# Survey_bicycle_Power.net
KiCad netlist of a schematic drawn in Altium Designer
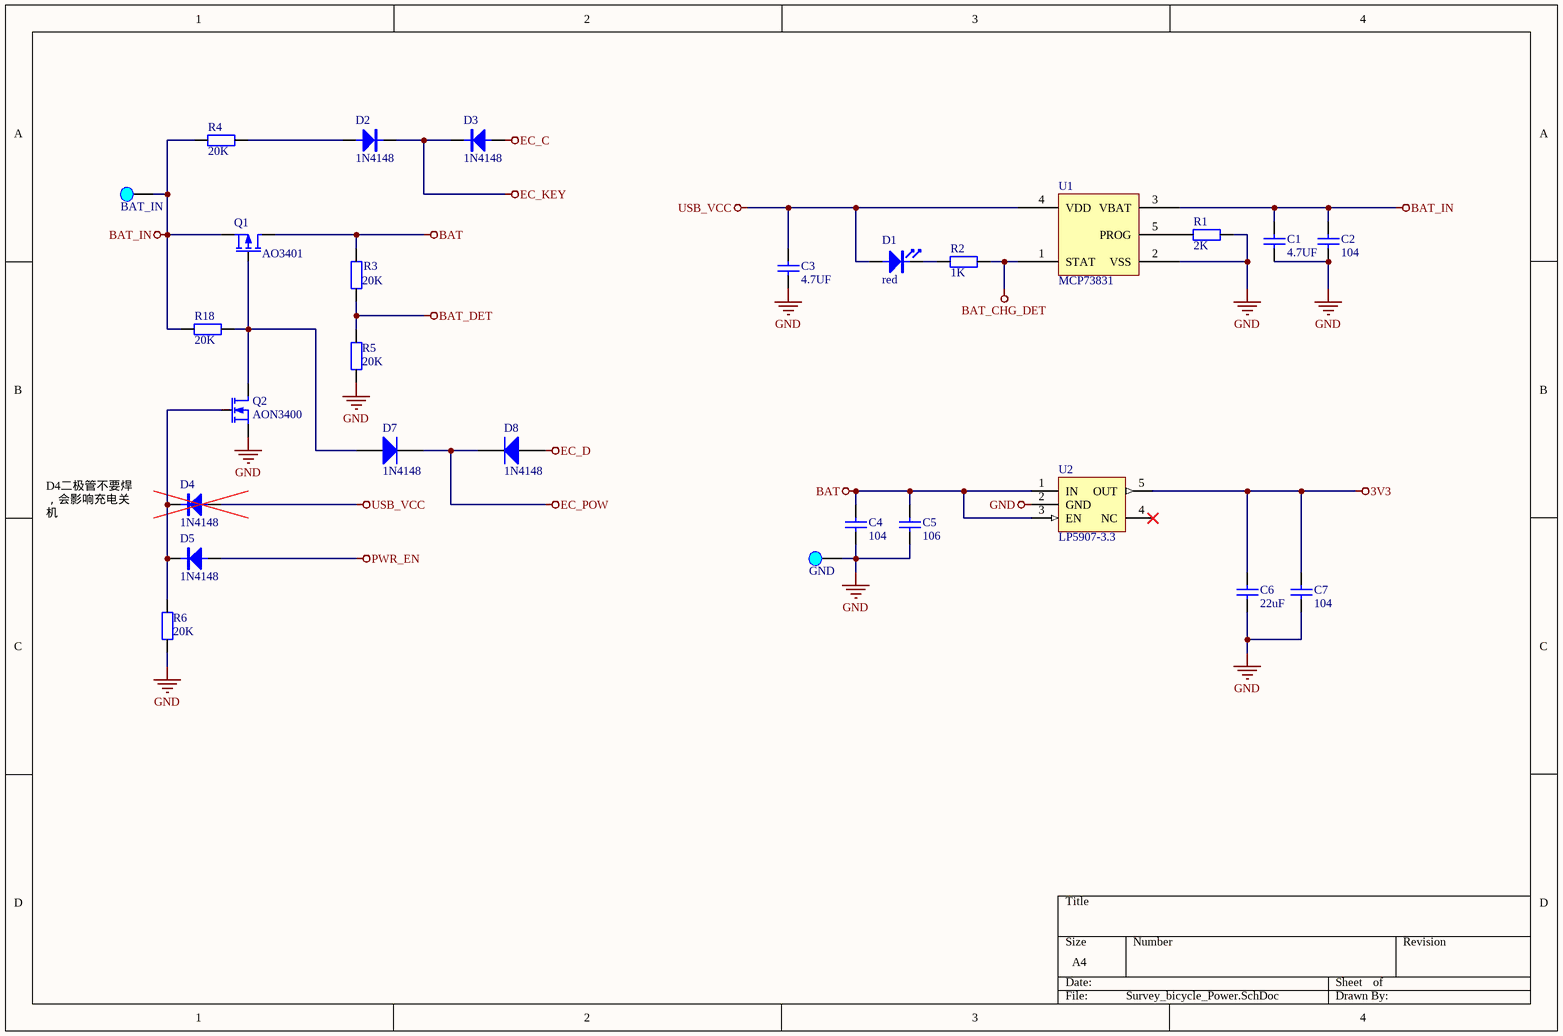
[diagram p0: Survey_bicycle_Power.SchDoc]

(export (version "E")
  (design (tool "Eeschema 10.0.6"))
  (components
    (comp (ref "BAT+")
      (value "BAT_IN")
      (footprint "Pad_B")
      (fields (field (name "_REMARKS") "BAT_IN"))
      (libsource (lib "元件库") (part "Pad"))
    )
    (comp (ref "BAT-")
      (value "GND")
      (footprint "Pad_B")
      (fields (field (name "_REMARKS") "GND"))
      (libsource (lib "元件库") (part "Pad"))
    )
    (comp (ref "C1")
      (value "4.7UF")
      (footprint "电容_C0805")
      (fields (field (name "C") "4.7UF"))
      (libsource (lib "元件库") (part "cap"))
    )
    (comp (ref "C2")
      (value "104")
      (footprint "电容_C0603")
      (fields (field (name "C") "104"))
      (libsource (lib "元件库") (part "cap"))
    )
    (comp (ref "C3")
      (value "4.7UF")
      (footprint "电容_C0805")
      (fields (field (name "C") "4.7UF"))
      (libsource (lib "元件库") (part "cap"))
    )
    (comp (ref "C4")
      (value "104")
      (footprint "电容_C0603")
      (fields (field (name "C") "104"))
      (libsource (lib "元件库") (part "cap"))
    )
    (comp (ref "C5")
      (value "106")
      (footprint "电容_C0603")
      (fields (field (name "C") "106"))
      (libsource (lib "元件库") (part "cap"))
    )
    (comp (ref "C6")
      (value "22uF")
      (footprint "电容_C1206")
      (fields (field (name "C") "22uF"))
      (libsource (lib "元件库") (part "cap"))
    )
    (comp (ref "C7")
      (value "104")
      (footprint "电容_C0603")
      (fields (field (name "C") "104"))
      (libsource (lib "元件库") (part "cap"))
    )
    (comp (ref "D1") (value "red") (footprint "LED_0603") (libsource (lib "元件库") (part "LED")))
    (comp (ref "D2")
      (value "1N4148")
      (footprint "二极管_SOD-323")
      (fields (field (name "_MODEL") "1N4148"))
      (libsource (lib "元件库") (part "Diode"))
    )
    (comp (ref "D3")
      (value "1N4148")
      (footprint "二极管_SOD-323")
      (fields (field (name "_MODEL") "1N4148"))
      (libsource (lib "元件库") (part "Diode"))
    )
    (comp (ref "D4")
      (value "1N4148")
      (footprint "二极管_SOD-323")
      (fields (field (name "_MODEL") "1N4148"))
      (libsource (lib "元件库") (part "Diode"))
    )
    (comp (ref "D5")
      (value "1N4148")
      (footprint "二极管_SOD-323")
      (fields (field (name "_MODEL") "1N4148"))
      (libsource (lib "元件库") (part "Diode"))
    )
    (comp (ref "D7")
      (value "1N4148")
      (footprint "SOD-323")
      (description "High Conductance Fast Diode")
      (fields (field (name "PUBLISHER") "Altium Limited"))
      (libsource (lib "Miscellaneous Devices") (part "Diode 1N4148"))
    )
    (comp (ref "D8")
      (value "1N4148")
      (footprint "SOD-323")
      (description "High Conductance Fast Diode")
      (fields (field (name "PUBLISHER") "Altium Limited"))
      (libsource (lib "Miscellaneous Devices") (part "Diode 1N4148"))
    )
    (comp (ref "Q1")
      (value "AO3401")
      (footprint "MOS_SOT-23")
      (fields (field (name "_MODEL") "AO3401"))
      (libsource (lib "元件库") (part "MOSFET-P"))
    )
    (comp (ref "Q2")
      (value "AON3400")
      (footprint "MOS_SOT-23")
      (fields (field (name "_MODEL") "AON3400"))
      (libsource (lib "元件库") (part "MOSFET-N"))
    )
    (comp (ref "R1")
      (value "2K")
      (footprint "电阻_R0603")
      (fields (field (name "R") "2K"))
      (libsource (lib "元件库") (part "Res"))
    )
    (comp (ref "R2")
      (value "1K")
      (footprint "电阻_R0603")
      (fields (field (name "R") "1K"))
      (libsource (lib "元件库") (part "Res"))
    )
    (comp (ref "R3")
      (value "20K")
      (footprint "电阻_R0603")
      (fields (field (name "R") "20K"))
      (libsource (lib "") (part "Res_2"))
    )
    (comp (ref "R4")
      (value "20K")
      (footprint "电阻_R0603")
      (fields (field (name "R") "20K"))
      (libsource (lib "") (part "Res_1"))
    )
    (comp (ref "R5")
      (value "20K")
      (footprint "电阻_R0603")
      (fields (field (name "R") "20K"))
      (libsource (lib "") (part "Res_2"))
    )
    (comp (ref "R6")
      (value "20K")
      (footprint "电阻_R0603")
      (fields (field (name "R") "20K"))
      (libsource (lib "") (part "Res_3"))
    )
    (comp (ref "R18")
      (value "20K")
      (footprint "R0603_L")
      (fields (field (name "R") "20K"))
      (libsource (lib "") (part "Res_1"))
    )
    (comp (ref "U1")
      (value "MCP73831")
      (footprint "SOT23-5")
      (description "线性充电管理控制器")
      (libsource (lib "TriggersLib") (part "MCP73831"))
    )
    (comp (ref "U2")
      (value "LP5907-3.3")
      (footprint "SOT23-5")
      (description "LDO")
      (libsource (lib "WatchX_TEST") (part "LP5907"))
    )
  )
  (nets
    (net (code "1") (name "3V3") (class "Default")
      (node (ref "C6") (pin "2") (pinfunction "2_2") (pintype "passive"))
      (node (ref "C7") (pin "2") (pinfunction "2_2") (pintype "passive"))
      (node (ref "U2") (pin "5") (pinfunction "OUT_5") (pintype "output"))
    )
    (net (code "2") (name "BAT") (class "Default")
      (node (ref "C4") (pin "2") (pinfunction "2_2") (pintype "passive"))
      (node (ref "C5") (pin "2") (pinfunction "2_2") (pintype "passive"))
      (node (ref "Q1") (pin "2") (pinfunction "D_2") (pintype "passive"))
      (node (ref "R3") (pin "2") (pinfunction "2_2") (pintype "passive"))
      (node (ref "U2") (pin "1") (pinfunction "IN_1") (pintype "power_in"))
      (node (ref "U2") (pin "3") (pinfunction "EN_3") (pintype "input"))
    )
    (net (code "3") (name "BAT_CHG_DET") (class "Default")
      (node (ref "R2") (pin "1") (pinfunction "1_1") (pintype "passive"))
      (node (ref "U1") (pin "1") (pinfunction "STAT_1") (pintype "passive"))
    )
    (net (code "4") (name "BAT_DET") (class "Default")
      (node (ref "R3") (pin "1") (pinfunction "1_1") (pintype "passive"))
      (node (ref "R5") (pin "2") (pinfunction "2_2") (pintype "passive"))
    )
    (net (code "5") (name "BAT_IN") (class "Default")
      (node (ref "BAT+") (pin "1") (pinfunction "*_1") (pintype "passive"))
      (node (ref "C1") (pin "2") (pinfunction "2_2") (pintype "passive"))
      (node (ref "C2") (pin "1") (pinfunction "1_1") (pintype "passive"))
      (node (ref "Q1") (pin "3") (pinfunction "S_3") (pintype "passive"))
      (node (ref "R18") (pin "1") (pinfunction "1_1") (pintype "passive"))
      (node (ref "R4") (pin "1") (pinfunction "1_1") (pintype "passive"))
      (node (ref "U1") (pin "3") (pinfunction "VBAT_3") (pintype "passive"))
    )
    (net (code "6") (name "EC_C") (class "Default")
      (node (ref "D3") (pin "A") (pinfunction "A_A") (pintype "passive"))
    )
    (net (code "7") (name "EC_D") (class "Default")
      (node (ref "D8") (pin "1") (pinfunction "A_1") (pintype "passive"))
    )
    (net (code "8") (name "EC_KEY") (class "Default")
      (node (ref "D2") (pin "K") (pinfunction "K_K") (pintype "passive"))
      (node (ref "D3") (pin "K") (pinfunction "K_K") (pintype "passive"))
    )
    (net (code "9") (name "EC_POW") (class "Default")
      (node (ref "D7") (pin "2") (pinfunction "K_2") (pintype "passive"))
      (node (ref "D8") (pin "2") (pinfunction "K_2") (pintype "passive"))
    )
    (net (code "10") (name "GND") (class "Default")
      (node (ref "BAT-") (pin "1") (pinfunction "*_1") (pintype "passive"))
      (node (ref "C1") (pin "1") (pinfunction "1_1") (pintype "passive"))
      (node (ref "C2") (pin "2") (pinfunction "2_2") (pintype "passive"))
      (node (ref "C3") (pin "1") (pinfunction "1_1") (pintype "passive"))
      (node (ref "C4") (pin "1") (pinfunction "1_1") (pintype "passive"))
      (node (ref "C5") (pin "1") (pinfunction "1_1") (pintype "passive"))
      (node (ref "C6") (pin "1") (pinfunction "1_1") (pintype "passive"))
      (node (ref "C7") (pin "1") (pinfunction "1_1") (pintype "passive"))
      (node (ref "Q2") (pin "3") (pinfunction "S_3") (pintype "passive"))
      (node (ref "R1") (pin "1") (pinfunction "1_1") (pintype "passive"))
      (node (ref "R5") (pin "1") (pinfunction "1_1") (pintype "passive"))
      (node (ref "R6") (pin "2") (pinfunction "2_2") (pintype "passive"))
      (node (ref "U1") (pin "2") (pinfunction "VSS_2") (pintype "passive"))
      (node (ref "U2") (pin "2") (pinfunction "GND_2") (pintype "passive"))
    )
    (net (code "11") (name "Net-(D1-PadK)") (class "Default")
      (node (ref "D1") (pin "K") (pinfunction "K_K") (pintype "passive"))
      (node (ref "R2") (pin "2") (pinfunction "2_2") (pintype "passive"))
    )
    (net (code "12") (name "Net-(D2-PadA)") (class "Default")
      (node (ref "D2") (pin "A") (pinfunction "A_A") (pintype "passive"))
      (node (ref "R4") (pin "2") (pinfunction "2_2") (pintype "passive"))
    )
    (net (code "13") (name "Net-(D7-A)") (class "Default")
      (node (ref "D7") (pin "1") (pinfunction "A_1") (pintype "passive"))
      (node (ref "Q1") (pin "1") (pinfunction "G_1") (pintype "passive"))
      (node (ref "Q2") (pin "2") (pinfunction "D_2") (pintype "passive"))
      (node (ref "R18") (pin "2") (pinfunction "2_2") (pintype "passive"))
    )
    (net (code "14") (name "Net-(Q2-G)") (class "Default")
      (node (ref "D4") (pin "K") (pinfunction "K_K") (pintype "passive"))
      (node (ref "D5") (pin "K") (pinfunction "K_K") (pintype "passive"))
      (node (ref "Q2") (pin "1") (pinfunction "G_1") (pintype "passive"))
      (node (ref "R6") (pin "1") (pinfunction "1_1") (pintype "passive"))
    )
    (net (code "15") (name "Net-(U1-PROG)") (class "Default")
      (node (ref "R1") (pin "2") (pinfunction "2_2") (pintype "passive"))
      (node (ref "U1") (pin "5") (pinfunction "PROG_5") (pintype "passive"))
    )
    (net (code "16") (name "PWR_EN") (class "Default")
      (node (ref "D5") (pin "A") (pinfunction "A_A") (pintype "passive"))
    )
    (net (code "17") (name "USB_VCC") (class "Default")
      (node (ref "C3") (pin "2") (pinfunction "2_2") (pintype "passive"))
      (node (ref "D1") (pin "A") (pinfunction "A_A") (pintype "passive"))
      (node (ref "D4") (pin "A") (pinfunction "A_A") (pintype "passive"))
      (node (ref "U1") (pin "4") (pinfunction "VDD_4") (pintype "passive"))
    )
    (net (code "18") (name "unconnected-(U2-NC-Pad4)") (class "Default")
      (node (ref "U2") (pin "4") (pinfunction "NC_4") (pintype "passive+no_connect"))
    )
  )
)
